# nikon-gps.net
KiCad netlist of a schematic drawn in EAGLE
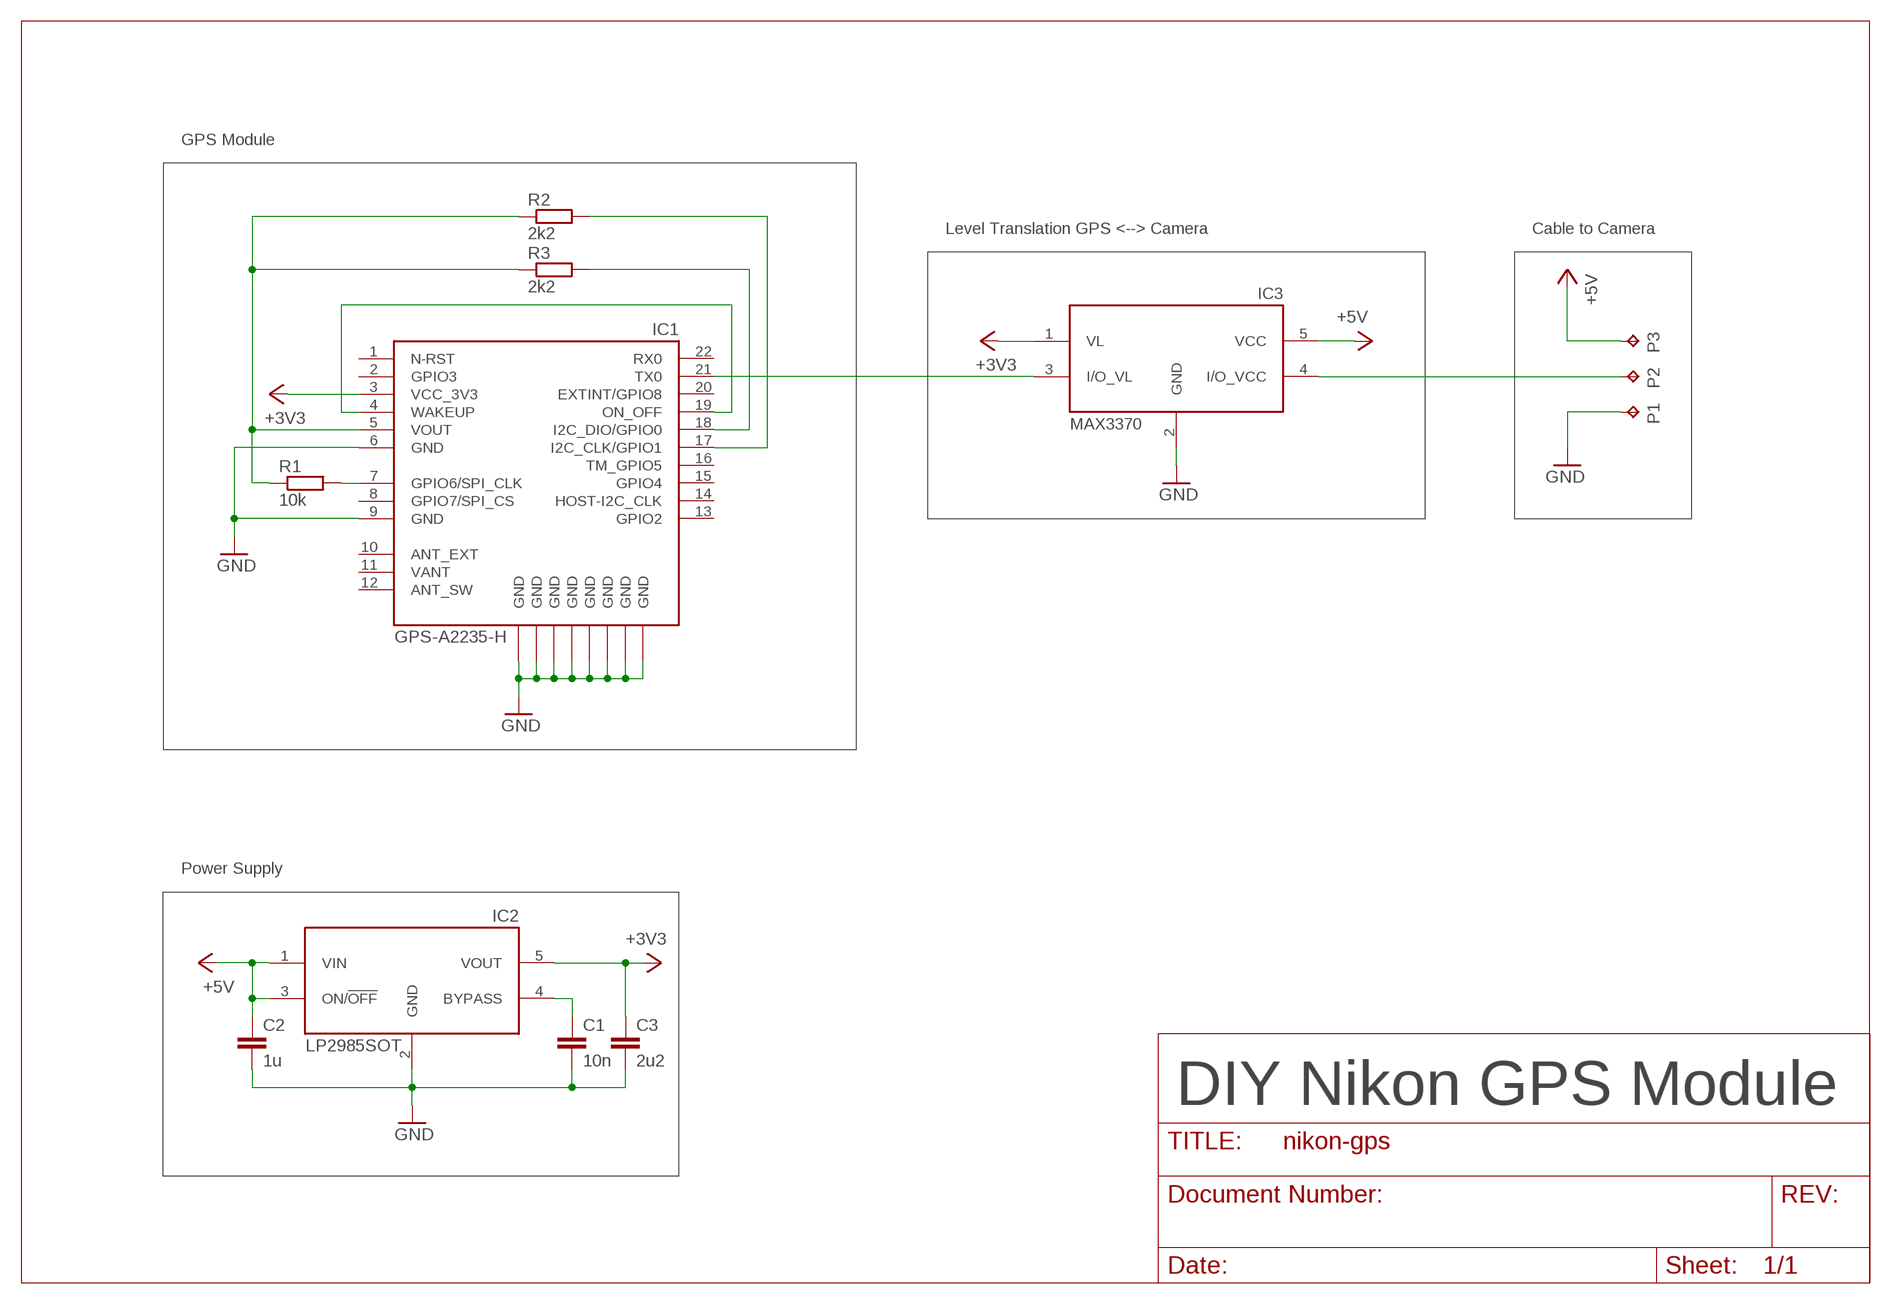
[diagram p0: schematic, sheet 1]

(export (version "E")
  (design (tool "Eeschema 10.0.6"))
  (components
    (comp (ref "C1")
      (value "10n")
      (footprint "eagle-import:C0805")
      (libsource (lib "eagle-import") (part "C-EUC0805"))
    )
    (comp (ref "C2")
      (value "1u")
      (footprint "eagle-import:C0805")
      (libsource (lib "eagle-import") (part "C-EUC0805"))
    )
    (comp (ref "C3")
      (value "2u2")
      (footprint "eagle-import:C0805")
      (libsource (lib "eagle-import") (part "C-EUC0805"))
    )
    (comp (ref "IC1")
      (value "GPS-A2235-H")
      (footprint "eagle-import:GPS-A2235-H")
      (libsource (lib "eagle-import") (part "GPS-A2235-H"))
    )
    (comp (ref "IC2")
      (value "LP2985SOT")
      (footprint "eagle-import:SOT23-5L")
      (libsource (lib "eagle-import") (part "LP2985SOT"))
    )
    (comp (ref "IC3")
      (value "MAX3370")
      (footprint "eagle-import:SC70-5L")
      (libsource (lib "eagle-import") (part "MAX3370"))
    )
    (comp (ref "P1")
      (value "TPTP12SQ")
      (footprint "eagle-import:TP12SQ")
      (libsource (lib "eagle-import") (part "TPTP12SQ"))
    )
    (comp (ref "P2")
      (value "TPTP12SQ")
      (footprint "eagle-import:TP12SQ")
      (libsource (lib "eagle-import") (part "TPTP12SQ"))
    )
    (comp (ref "P3")
      (value "TPTP12SQ")
      (footprint "eagle-import:TP12SQ")
      (libsource (lib "eagle-import") (part "TPTP12SQ"))
    )
    (comp (ref "R1")
      (value "10k")
      (footprint "eagle-import:M1206")
      (libsource (lib "eagle-import") (part "R-EU_M1206"))
    )
    (comp (ref "R2")
      (value "2k2")
      (footprint "eagle-import:M1206")
      (libsource (lib "eagle-import") (part "R-EU_M1206"))
    )
    (comp (ref "R3")
      (value "2k2")
      (footprint "eagle-import:M1206")
      (libsource (lib "eagle-import") (part "R-EU_M1206"))
    )
  )
  (nets
    (net (code "1") (name "+3V3") (class "Default")
      (node (ref "C3") (pin "1") (pinfunction "1_1") (pintype "passive"))
      (node (ref "IC1") (pin "3") (pinfunction "VCC_3V3_3") (pintype "power_in"))
      (node (ref "IC2") (pin "5") (pinfunction "VOUT_5") (pintype "power_in"))
      (node (ref "IC3") (pin "1") (pinfunction "VL_1") (pintype "power_in"))
    )
    (net (code "2") (name "+5V") (class "Default")
      (node (ref "C2") (pin "1") (pinfunction "1_1") (pintype "passive"))
      (node (ref "IC2") (pin "1") (pinfunction "VIN_1") (pintype "power_in"))
      (node (ref "IC2") (pin "3") (pinfunction "ON/~{OFF}_3") (pintype "input"))
      (node (ref "IC3") (pin "5") (pinfunction "VCC_5") (pintype "power_in"))
      (node (ref "P3") (pin "TP") (pinfunction "TP_TP") (pintype "input"))
    )
    (net (code "3") (name "/VANT") (class "Default")
      (node (ref "IC1") (pin "11") (pinfunction "VANT_11") (pintype "power_in"))
    )
    (net (code "4") (name "GND") (class "Default")
      (node (ref "C1") (pin "2") (pinfunction "2_2") (pintype "passive"))
      (node (ref "C2") (pin "2") (pinfunction "2_2") (pintype "passive"))
      (node (ref "C3") (pin "2") (pinfunction "2_2") (pintype "passive"))
      (node (ref "IC1") (pin "6") (pinfunction "GND_6") (pintype "power_in"))
      (node (ref "IC1") (pin "9") (pinfunction "GND_9") (pintype "power_in"))
      (node (ref "IC1") (pin "GND_PAD@1") (pinfunction "GND_GND_PAD@1") (pintype "power_in"))
      (node (ref "IC1") (pin "GND_PAD@2") (pinfunction "GND_GND_PAD@2") (pintype "power_in"))
      (node (ref "IC1") (pin "GND_PAD@3") (pinfunction "GND_GND_PAD@3") (pintype "power_in"))
      (node (ref "IC1") (pin "GND_PAD@4") (pinfunction "GND_GND_PAD@4") (pintype "power_in"))
      (node (ref "IC1") (pin "GND_PAD@5") (pinfunction "GND_GND_PAD@5") (pintype "power_in"))
      (node (ref "IC1") (pin "GND_PAD@6") (pinfunction "GND_GND_PAD@6") (pintype "power_in"))
      (node (ref "IC1") (pin "GND_PAD@7") (pinfunction "GND_GND_PAD@7") (pintype "power_in"))
      (node (ref "IC1") (pin "GND_PAD@8") (pinfunction "GND_GND_PAD@8") (pintype "power_in"))
      (node (ref "IC2") (pin "2") (pinfunction "GND_2") (pintype "power_in"))
      (node (ref "IC3") (pin "2") (pinfunction "GND_2") (pintype "power_in"))
      (node (ref "P1") (pin "TP") (pinfunction "TP_TP") (pintype "input"))
    )
    (net (code "5") (name "Net-(IC1-GPIO6{slash}SPI_CLK)") (class "Default")
      (node (ref "IC1") (pin "7") (pinfunction "GPIO6/SPI_CLK_7") (pintype "input"))
      (node (ref "R1") (pin "2") (pinfunction "2_2") (pintype "passive"))
    )
    (net (code "6") (name "Net-(IC1-I2C_CLK{slash}GPIO1)") (class "Default")
      (node (ref "IC1") (pin "17") (pinfunction "I2C_CLK/GPIO1_17") (pintype "bidirectional"))
      (node (ref "R2") (pin "2") (pinfunction "2_2") (pintype "passive"))
    )
    (net (code "7") (name "Net-(IC1-I2C_DIO{slash}GPIO0)") (class "Default")
      (node (ref "IC1") (pin "18") (pinfunction "I2C_DIO/GPIO0_18") (pintype "bidirectional"))
      (node (ref "R3") (pin "2") (pinfunction "2_2") (pintype "passive"))
    )
    (net (code "8") (name "Net-(IC1-ON_OFF)") (class "Default")
      (node (ref "IC1") (pin "19") (pinfunction "ON_OFF_19") (pintype "input"))
      (node (ref "IC1") (pin "4") (pinfunction "WAKEUP_4") (pintype "output"))
    )
    (net (code "9") (name "Net-(IC1-TX0)") (class "Default")
      (node (ref "IC1") (pin "21") (pinfunction "TX0_21") (pintype "output"))
      (node (ref "IC3") (pin "3") (pinfunction "I/O_VL_3") (pintype "open_collector"))
    )
    (net (code "10") (name "Net-(IC1-VOUT)") (class "Default")
      (node (ref "IC1") (pin "5") (pinfunction "VOUT_5") (pintype "power_in"))
      (node (ref "R1") (pin "1") (pinfunction "1_1") (pintype "passive"))
      (node (ref "R2") (pin "1") (pinfunction "1_1") (pintype "passive"))
      (node (ref "R3") (pin "1") (pinfunction "1_1") (pintype "passive"))
    )
    (net (code "11") (name "Net-(IC2-BYPASS)") (class "Default")
      (node (ref "C1") (pin "1") (pinfunction "1_1") (pintype "passive"))
      (node (ref "IC2") (pin "4") (pinfunction "BYPASS_4") (pintype "bidirectional"))
    )
    (net (code "12") (name "Net-(IC3-I{slash}O_VCC)") (class "Default")
      (node (ref "IC3") (pin "4") (pinfunction "I/O_VCC_4") (pintype "open_collector"))
      (node (ref "P2") (pin "TP") (pinfunction "TP_TP") (pintype "input"))
    )
    (net (code "13") (name "unconnected-(IC1-ANT_EXT-Pad10)") (class "Default")
      (node (ref "IC1") (pin "10") (pinfunction "ANT_EXT_10") (pintype "input"))
    )
    (net (code "14") (name "unconnected-(IC1-ANT_SW-Pad12)") (class "Default")
      (node (ref "IC1") (pin "12") (pinfunction "ANT_SW_12") (pintype "input"))
    )
    (net (code "15") (name "unconnected-(IC1-EXTINT{slash}GPIO8-Pad20)") (class "Default")
      (node (ref "IC1") (pin "20") (pinfunction "EXTINT/GPIO8_20") (pintype "input"))
    )
    (net (code "16") (name "unconnected-(IC1-GPIO2-Pad13)") (class "Default")
      (node (ref "IC1") (pin "13") (pinfunction "GPIO2_13") (pintype "no_connect"))
    )
    (net (code "17") (name "unconnected-(IC1-GPIO3-Pad2)") (class "Default")
      (node (ref "IC1") (pin "2") (pinfunction "GPIO3_2") (pintype "no_connect"))
    )
    (net (code "18") (name "unconnected-(IC1-GPIO4-Pad15)") (class "Default")
      (node (ref "IC1") (pin "15") (pinfunction "GPIO4_15") (pintype "input"))
    )
    (net (code "19") (name "unconnected-(IC1-GPIO7{slash}SPI_CS-Pad8)") (class "Default")
      (node (ref "IC1") (pin "8") (pinfunction "GPIO7/SPI_CS_8") (pintype "input"))
    )
    (net (code "20") (name "unconnected-(IC1-HOST-I2C_CLK-Pad14)") (class "Default")
      (node (ref "IC1") (pin "14") (pinfunction "HOST-I2C_CLK_14") (pintype "input"))
    )
    (net (code "21") (name "unconnected-(IC1-N-RST-Pad1)") (class "Default")
      (node (ref "IC1") (pin "1") (pinfunction "N-RST_1") (pintype "input"))
    )
    (net (code "22") (name "unconnected-(IC1-RX0-Pad22)") (class "Default")
      (node (ref "IC1") (pin "22") (pinfunction "RX0_22") (pintype "input"))
    )
    (net (code "23") (name "unconnected-(IC1-TM_GPIO5-Pad16)") (class "Default")
      (node (ref "IC1") (pin "16") (pinfunction "TM_GPIO5_16") (pintype "output"))
    )
  )
)
